# FEEDERLINK.net
KiCad netlist of a schematic drawn in EAGLE
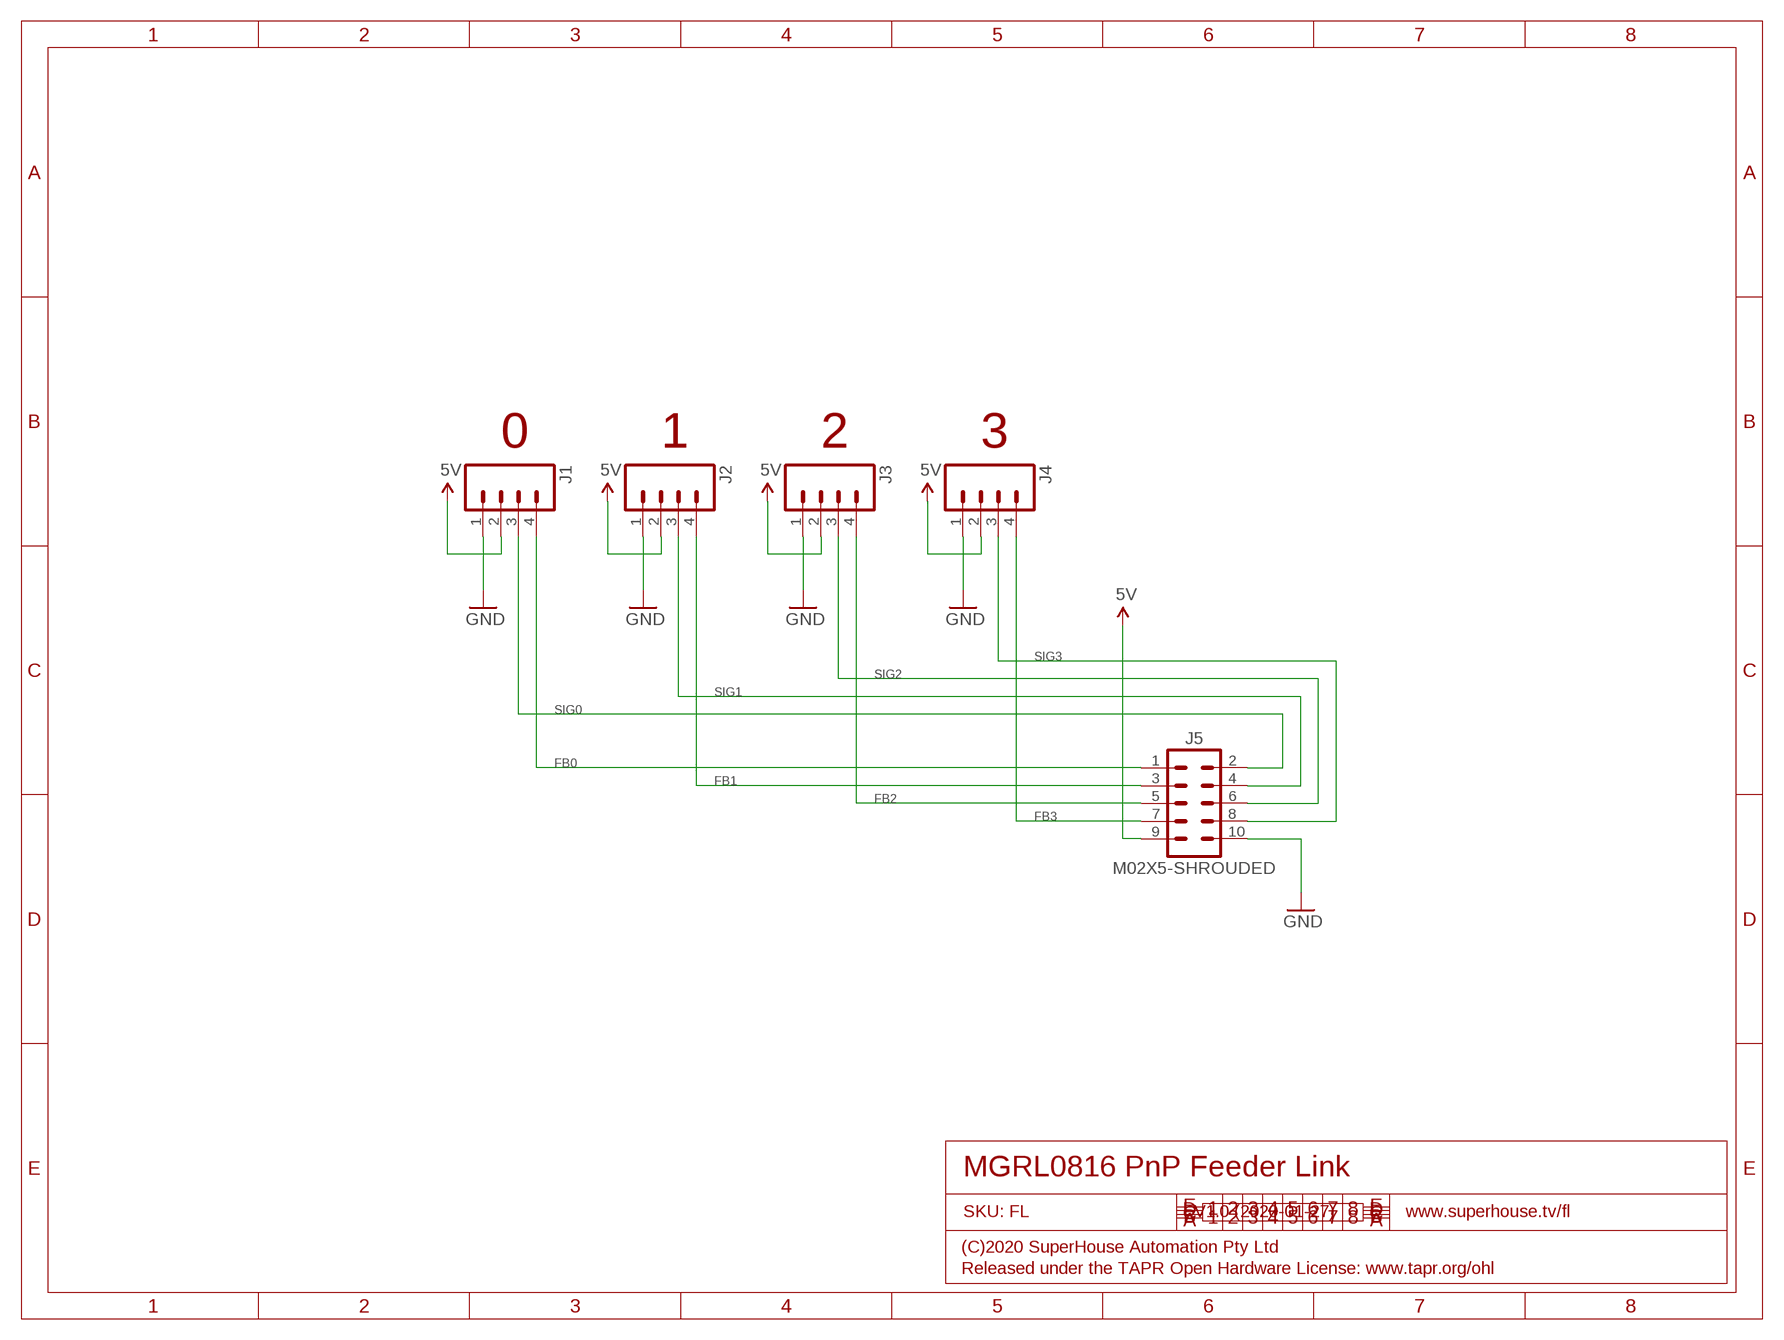
[diagram p0: schematic, sheet 1]

(export (version "E")
  (design (tool "Eeschema 10.0.6"))
  (components
    (comp (ref "J1")
      (value "M04-SOCKET")
      (footprint "eagle-import:1X04-S")
      (libsource (lib "eagle-import") (part "M04-SOCKET"))
    )
    (comp (ref "J2")
      (value "M04-SOCKET")
      (footprint "eagle-import:1X04-S")
      (libsource (lib "eagle-import") (part "M04-SOCKET"))
    )
    (comp (ref "J3")
      (value "M04-SOCKET")
      (footprint "eagle-import:1X04-S")
      (libsource (lib "eagle-import") (part "M04-SOCKET"))
    )
    (comp (ref "J4")
      (value "M04-SOCKET")
      (footprint "eagle-import:1X04-S")
      (libsource (lib "eagle-import") (part "M04-SOCKET"))
    )
    (comp (ref "J5")
      (value "M02X5-SHROUDED")
      (footprint "eagle-import:2X05-2.54-SHROUDED")
      (libsource (lib "eagle-import") (part "M02X5-SHROUDED"))
    )
  )
  (nets
    (net (code "1") (name "/FB0") (class "Default")
      (node (ref "J1") (pin "4") (pinfunction "4_4") (pintype "passive"))
      (node (ref "J5") (pin "1") (pinfunction "1_1") (pintype "passive"))
    )
    (net (code "2") (name "/FB1") (class "Default")
      (node (ref "J2") (pin "4") (pinfunction "4_4") (pintype "passive"))
      (node (ref "J5") (pin "3") (pinfunction "3_3") (pintype "passive"))
    )
    (net (code "3") (name "/FB2") (class "Default")
      (node (ref "J3") (pin "4") (pinfunction "4_4") (pintype "passive"))
      (node (ref "J5") (pin "5") (pinfunction "5_5") (pintype "passive"))
    )
    (net (code "4") (name "/FB3") (class "Default")
      (node (ref "J4") (pin "4") (pinfunction "4_4") (pintype "passive"))
      (node (ref "J5") (pin "7") (pinfunction "7_7") (pintype "passive"))
    )
    (net (code "5") (name "/SIG0") (class "Default")
      (node (ref "J1") (pin "3") (pinfunction "3_3") (pintype "passive"))
      (node (ref "J5") (pin "2") (pinfunction "2_2") (pintype "passive"))
    )
    (net (code "6") (name "/SIG1") (class "Default")
      (node (ref "J2") (pin "3") (pinfunction "3_3") (pintype "passive"))
      (node (ref "J5") (pin "4") (pinfunction "4_4") (pintype "passive"))
    )
    (net (code "7") (name "/SIG2") (class "Default")
      (node (ref "J3") (pin "3") (pinfunction "3_3") (pintype "passive"))
      (node (ref "J5") (pin "6") (pinfunction "6_6") (pintype "passive"))
    )
    (net (code "8") (name "/SIG3") (class "Default")
      (node (ref "J4") (pin "3") (pinfunction "3_3") (pintype "passive"))
      (node (ref "J5") (pin "8") (pinfunction "8_8") (pintype "passive"))
    )
    (net (code "9") (name "5V") (class "Default")
      (node (ref "J1") (pin "2") (pinfunction "2_2") (pintype "passive"))
      (node (ref "J2") (pin "2") (pinfunction "2_2") (pintype "passive"))
      (node (ref "J3") (pin "2") (pinfunction "2_2") (pintype "passive"))
      (node (ref "J4") (pin "2") (pinfunction "2_2") (pintype "passive"))
      (node (ref "J5") (pin "9") (pinfunction "9_9") (pintype "passive"))
    )
    (net (code "10") (name "GND") (class "Default")
      (node (ref "J1") (pin "1") (pinfunction "1_1") (pintype "passive"))
      (node (ref "J2") (pin "1") (pinfunction "1_1") (pintype "passive"))
      (node (ref "J3") (pin "1") (pinfunction "1_1") (pintype "passive"))
      (node (ref "J4") (pin "1") (pinfunction "1_1") (pintype "passive"))
      (node (ref "J5") (pin "10") (pinfunction "10_10") (pintype "passive"))
    )
  )
)
